# ButtonDriver.net
KiCad netlist of a schematic drawn in EAGLE
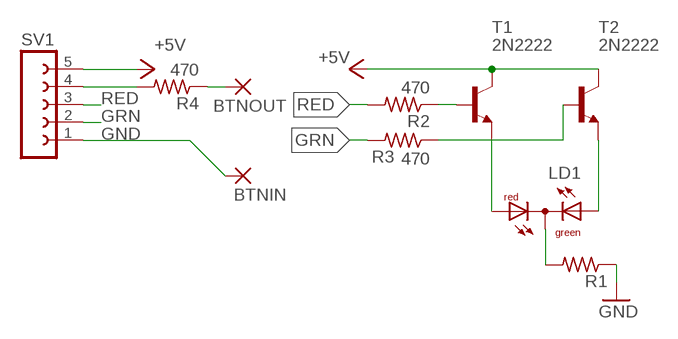
[diagram p0: schematic, sheet 1]

(export (version "E")
  (design (tool "Eeschema 10.0.6"))
  (components
    (comp (ref "BTNIN")
      (value "2,54/0,9")
      (footprint "eagle-import:2,54_0,9")
      (libsource (lib "eagle-import") (part "2,54/0,9"))
    )
    (comp (ref "BTNOUT")
      (value "2,54/0,9")
      (footprint "eagle-import:2,54_0,9")
      (libsource (lib "eagle-import") (part "2,54/0,9"))
    )
    (comp (ref "LD1")
      (value "DUOLED-RG-C")
      (footprint "eagle-import:DUOLED-C-5MM")
      (libsource (lib "eagle-import") (part "DUOLED-RG-C"))
    )
    (comp (ref "R1")
      (value "R-US_0207/10")
      (footprint "eagle-import:0207_10")
      (libsource (lib "eagle-import") (part "R-US_0207/10"))
    )
    (comp (ref "R2")
      (value "470")
      (footprint "eagle-import:0207_10")
      (libsource (lib "eagle-import") (part "R-US_0207/10"))
    )
    (comp (ref "R3")
      (value "470")
      (footprint "eagle-import:0207_10")
      (libsource (lib "eagle-import") (part "R-US_0207/10"))
    )
    (comp (ref "R4")
      (value "470")
      (footprint "eagle-import:0207_10")
      (libsource (lib "eagle-import") (part "R-US_0207/10"))
    )
    (comp (ref "SV1")
      (value "FE05-1")
      (footprint "eagle-import:FE05-1")
      (libsource (lib "eagle-import") (part "FE05-1"))
    )
    (comp (ref "T1")
      (value "2N2222")
      (footprint "eagle-import:TO92-EBC-OVAL")
      (libsource (lib "eagle-import") (part "2N2222"))
    )
    (comp (ref "T2")
      (value "2N2222")
      (footprint "eagle-import:TO92-EBC-OVAL")
      (libsource (lib "eagle-import") (part "2N2222"))
    )
  )
  (nets
    (net (code "1") (name "+5V") (class "Default")
      (node (ref "SV1") (pin "5") (pinfunction "5_5") (pintype "passive"))
      (node (ref "T1") (pin "C") (pinfunction "C_C") (pintype "passive"))
      (node (ref "T2") (pin "C") (pinfunction "C_C") (pintype "passive"))
    )
    (net (code "2") (name "GND") (class "Default")
      (node (ref "BTNIN") (pin "1") (pinfunction "P_1") (pintype "passive"))
      (node (ref "R1") (pin "1") (pinfunction "1_1") (pintype "passive"))
      (node (ref "SV1") (pin "1") (pinfunction "1_1") (pintype "passive"))
    )
    (net (code "3") (name "GRN") (class "Default")
      (node (ref "R3") (pin "2") (pinfunction "2_2") (pintype "passive"))
      (node (ref "SV1") (pin "2") (pinfunction "2_2") (pintype "passive"))
    )
    (net (code "4") (name "Net-(BTNOUT-P)") (class "Default")
      (node (ref "BTNOUT") (pin "1") (pinfunction "P_1") (pintype "passive"))
      (node (ref "R4") (pin "1") (pinfunction "1_1") (pintype "passive"))
    )
    (net (code "5") (name "Net-(LD1-AG)") (class "Default")
      (node (ref "LD1") (pin "AX") (pinfunction "AG_AX") (pintype "passive"))
      (node (ref "T2") (pin "E") (pinfunction "E_E") (pintype "passive"))
    )
    (net (code "6") (name "Net-(LD1-PadAR)") (class "Default")
      (node (ref "LD1") (pin "AR") (pinfunction "AR_AR") (pintype "passive"))
      (node (ref "T1") (pin "E") (pinfunction "E_E") (pintype "passive"))
    )
    (net (code "7") (name "Net-(LD1-PadC)") (class "Default")
      (node (ref "LD1") (pin "C") (pinfunction "C_C") (pintype "passive"))
      (node (ref "R1") (pin "2") (pinfunction "2_2") (pintype "passive"))
    )
    (net (code "8") (name "Net-(R2-Pad1)") (class "Default")
      (node (ref "R2") (pin "1") (pinfunction "1_1") (pintype "passive"))
      (node (ref "T1") (pin "B") (pinfunction "B_B") (pintype "passive"))
    )
    (net (code "9") (name "Net-(R3-Pad1)") (class "Default")
      (node (ref "R3") (pin "1") (pinfunction "1_1") (pintype "passive"))
      (node (ref "T2") (pin "B") (pinfunction "B_B") (pintype "passive"))
    )
    (net (code "10") (name "Net-(R4-Pad2)") (class "Default")
      (node (ref "R4") (pin "2") (pinfunction "2_2") (pintype "passive"))
      (node (ref "SV1") (pin "4") (pinfunction "4_4") (pintype "passive"))
    )
    (net (code "11") (name "RED") (class "Default")
      (node (ref "R2") (pin "2") (pinfunction "2_2") (pintype "passive"))
      (node (ref "SV1") (pin "3") (pinfunction "3_3") (pintype "passive"))
    )
  )
)
